# bela_expansion_card_1.net
KiCad netlist of a schematic drawn in Altium Designer
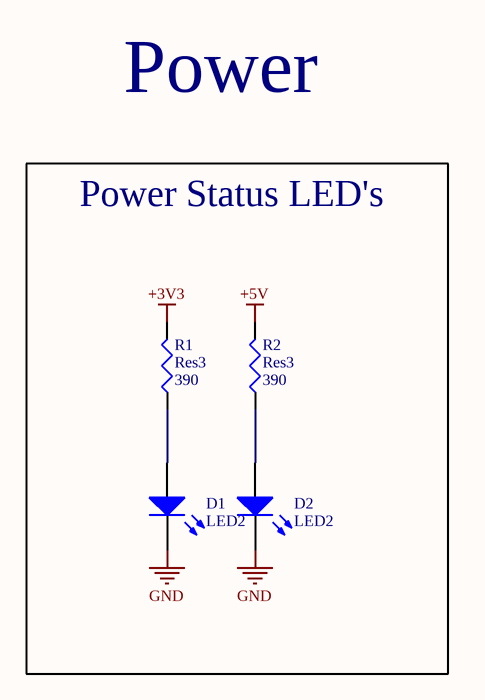
[diagram p0: bela_expansion_card_1.SchDoc]

(export (version "E")
  (design (tool "Eeschema 10.0.6"))
  (components
    (comp (ref "D1")
      (value "LED2")
      (footprint "3.2X1.6X1.1")
      (description "Typical RED, GREEN, YELLOW, AMBER GaAs LED")
      (fields (field (name "PUBLISHER") "Altium Limited"))
      (libsource (lib "EE_Emerge_SkillsProject") (part "LED2"))
    )
    (comp (ref "D2")
      (value "LED2")
      (footprint "3.2X1.6X1.1")
      (description "Typical RED, GREEN, YELLOW, AMBER GaAs LED")
      (fields (field (name "PUBLISHER") "Altium Limited"))
      (libsource (lib "EE_Emerge_SkillsProject") (part "LED2"))
    )
    (comp (ref "R1")
      (value "Res3")
      (footprint "6-0805_L")
      (description "Resistor")
      (fields (field (name "ALTIUM_VALUE") "390") (field (name "PUBLISHER") "Altium Limited"))
      (libsource (lib "EE_Emerge_SkillsProject") (part "Res3"))
    )
    (comp (ref "R2")
      (value "Res3")
      (footprint "6-0805_L")
      (description "Resistor")
      (fields (field (name "ALTIUM_VALUE") "390") (field (name "PUBLISHER") "Altium Limited"))
      (libsource (lib "EE_Emerge_SkillsProject") (part "Res3"))
    )
  )
  (nets
    (net (code "1") (name "+3V3") (class "Default")
      (node (ref "R1") (pin "2") (pinfunction "2_2") (pintype "passive"))
    )
    (net (code "2") (name "+5V") (class "Default")
      (node (ref "R2") (pin "2") (pinfunction "2_2") (pintype "passive"))
    )
    (net (code "3") (name "GND") (class "Default")
      (node (ref "D1") (pin "2") (pinfunction "K_2") (pintype "passive"))
      (node (ref "D2") (pin "2") (pinfunction "K_2") (pintype "passive"))
    )
    (net (code "4") (name "Net-(D1-A)") (class "Default")
      (node (ref "D1") (pin "1") (pinfunction "A_1") (pintype "passive"))
      (node (ref "R1") (pin "1") (pinfunction "1_1") (pintype "passive"))
    )
    (net (code "5") (name "Net-(D2-A)") (class "Default")
      (node (ref "D2") (pin "1") (pinfunction "A_1") (pintype "passive"))
      (node (ref "R2") (pin "1") (pinfunction "1_1") (pintype "passive"))
    )
  )
)
